# ESE-22MH_Breakout.net
KiCad netlist of a schematic drawn in EAGLE
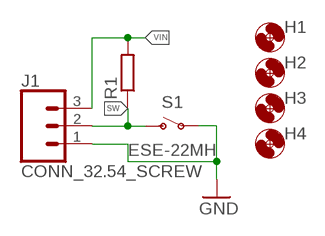
[diagram p0: schematic, sheet 1]

(export (version "E")
  (design (tool "Eeschema 10.0.6"))
  (components
    (comp (ref "H1")
      (value "MOUNTING_HOLE4_NP")
      (footprint "eagle-import:4_40")
      (fields (field (name "MPN") "DNP"))
      (libsource (lib "eagle-import") (part "MOUNTING_HOLE4_NP"))
    )
    (comp (ref "H2")
      (value "MOUNTING_HOLE4_NP")
      (footprint "eagle-import:4_40")
      (fields (field (name "MPN") "DNP"))
      (libsource (lib "eagle-import") (part "MOUNTING_HOLE4_NP"))
    )
    (comp (ref "H3")
      (value "MOUNTING_HOLE4_NP")
      (footprint "eagle-import:4_40")
      (fields (field (name "MPN") "DNP"))
      (libsource (lib "eagle-import") (part "MOUNTING_HOLE4_NP"))
    )
    (comp (ref "H4")
      (value "MOUNTING_HOLE4_NP")
      (footprint "eagle-import:4_40")
      (fields (field (name "MPN") "DNP"))
      (libsource (lib "eagle-import") (part "MOUNTING_HOLE4_NP"))
    )
    (comp (ref "J1")
      (value "CONN_32.54_SCREW")
      (footprint "eagle-import:1X03_SCREW")
      (fields (field (name "MF") "On Shore") (field (name "MPN") "OSTVN03A150"))
      (libsource (lib "eagle-import") (part "CONN_32.54_SCREW"))
    )
    (comp (ref "R1")
      (value "R-EU_R0603")
      (footprint "eagle-import:R0603")
      (fields (field (name "MF") "Yageo"))
      (libsource (lib "eagle-import") (part "R-EU_R0603"))
    )
    (comp (ref "S1")
      (value "ESE-22MH")
      (footprint "eagle-import:ESE-22MH")
      (fields (field (name "MF") "Panasonic") (field (name "MPN") "ESE-22MH24"))
      (libsource (lib "eagle-import") (part "SPSTESE-22MH"))
    )
  )
  (nets
    (net (code "1") (name "GND") (class "Default")
      (node (ref "J1") (pin "1") (pinfunction "1_1") (pintype "passive"))
      (node (ref "S1") (pin "2") (pinfunction "P_2") (pintype "passive"))
    )
    (net (code "2") (name "SW") (class "Default")
      (node (ref "J1") (pin "2") (pinfunction "2_2") (pintype "passive"))
      (node (ref "R1") (pin "1") (pinfunction "1_1") (pintype "passive"))
      (node (ref "S1") (pin "1") (pinfunction "O_1") (pintype "passive"))
    )
    (net (code "3") (name "VIN") (class "Default")
      (node (ref "J1") (pin "3") (pinfunction "3_3") (pintype "passive"))
      (node (ref "R1") (pin "2") (pinfunction "2_2") (pintype "passive"))
    )
  )
)
